# Current_Measurement.net
KiCad netlist of a schematic drawn in Altium Designer
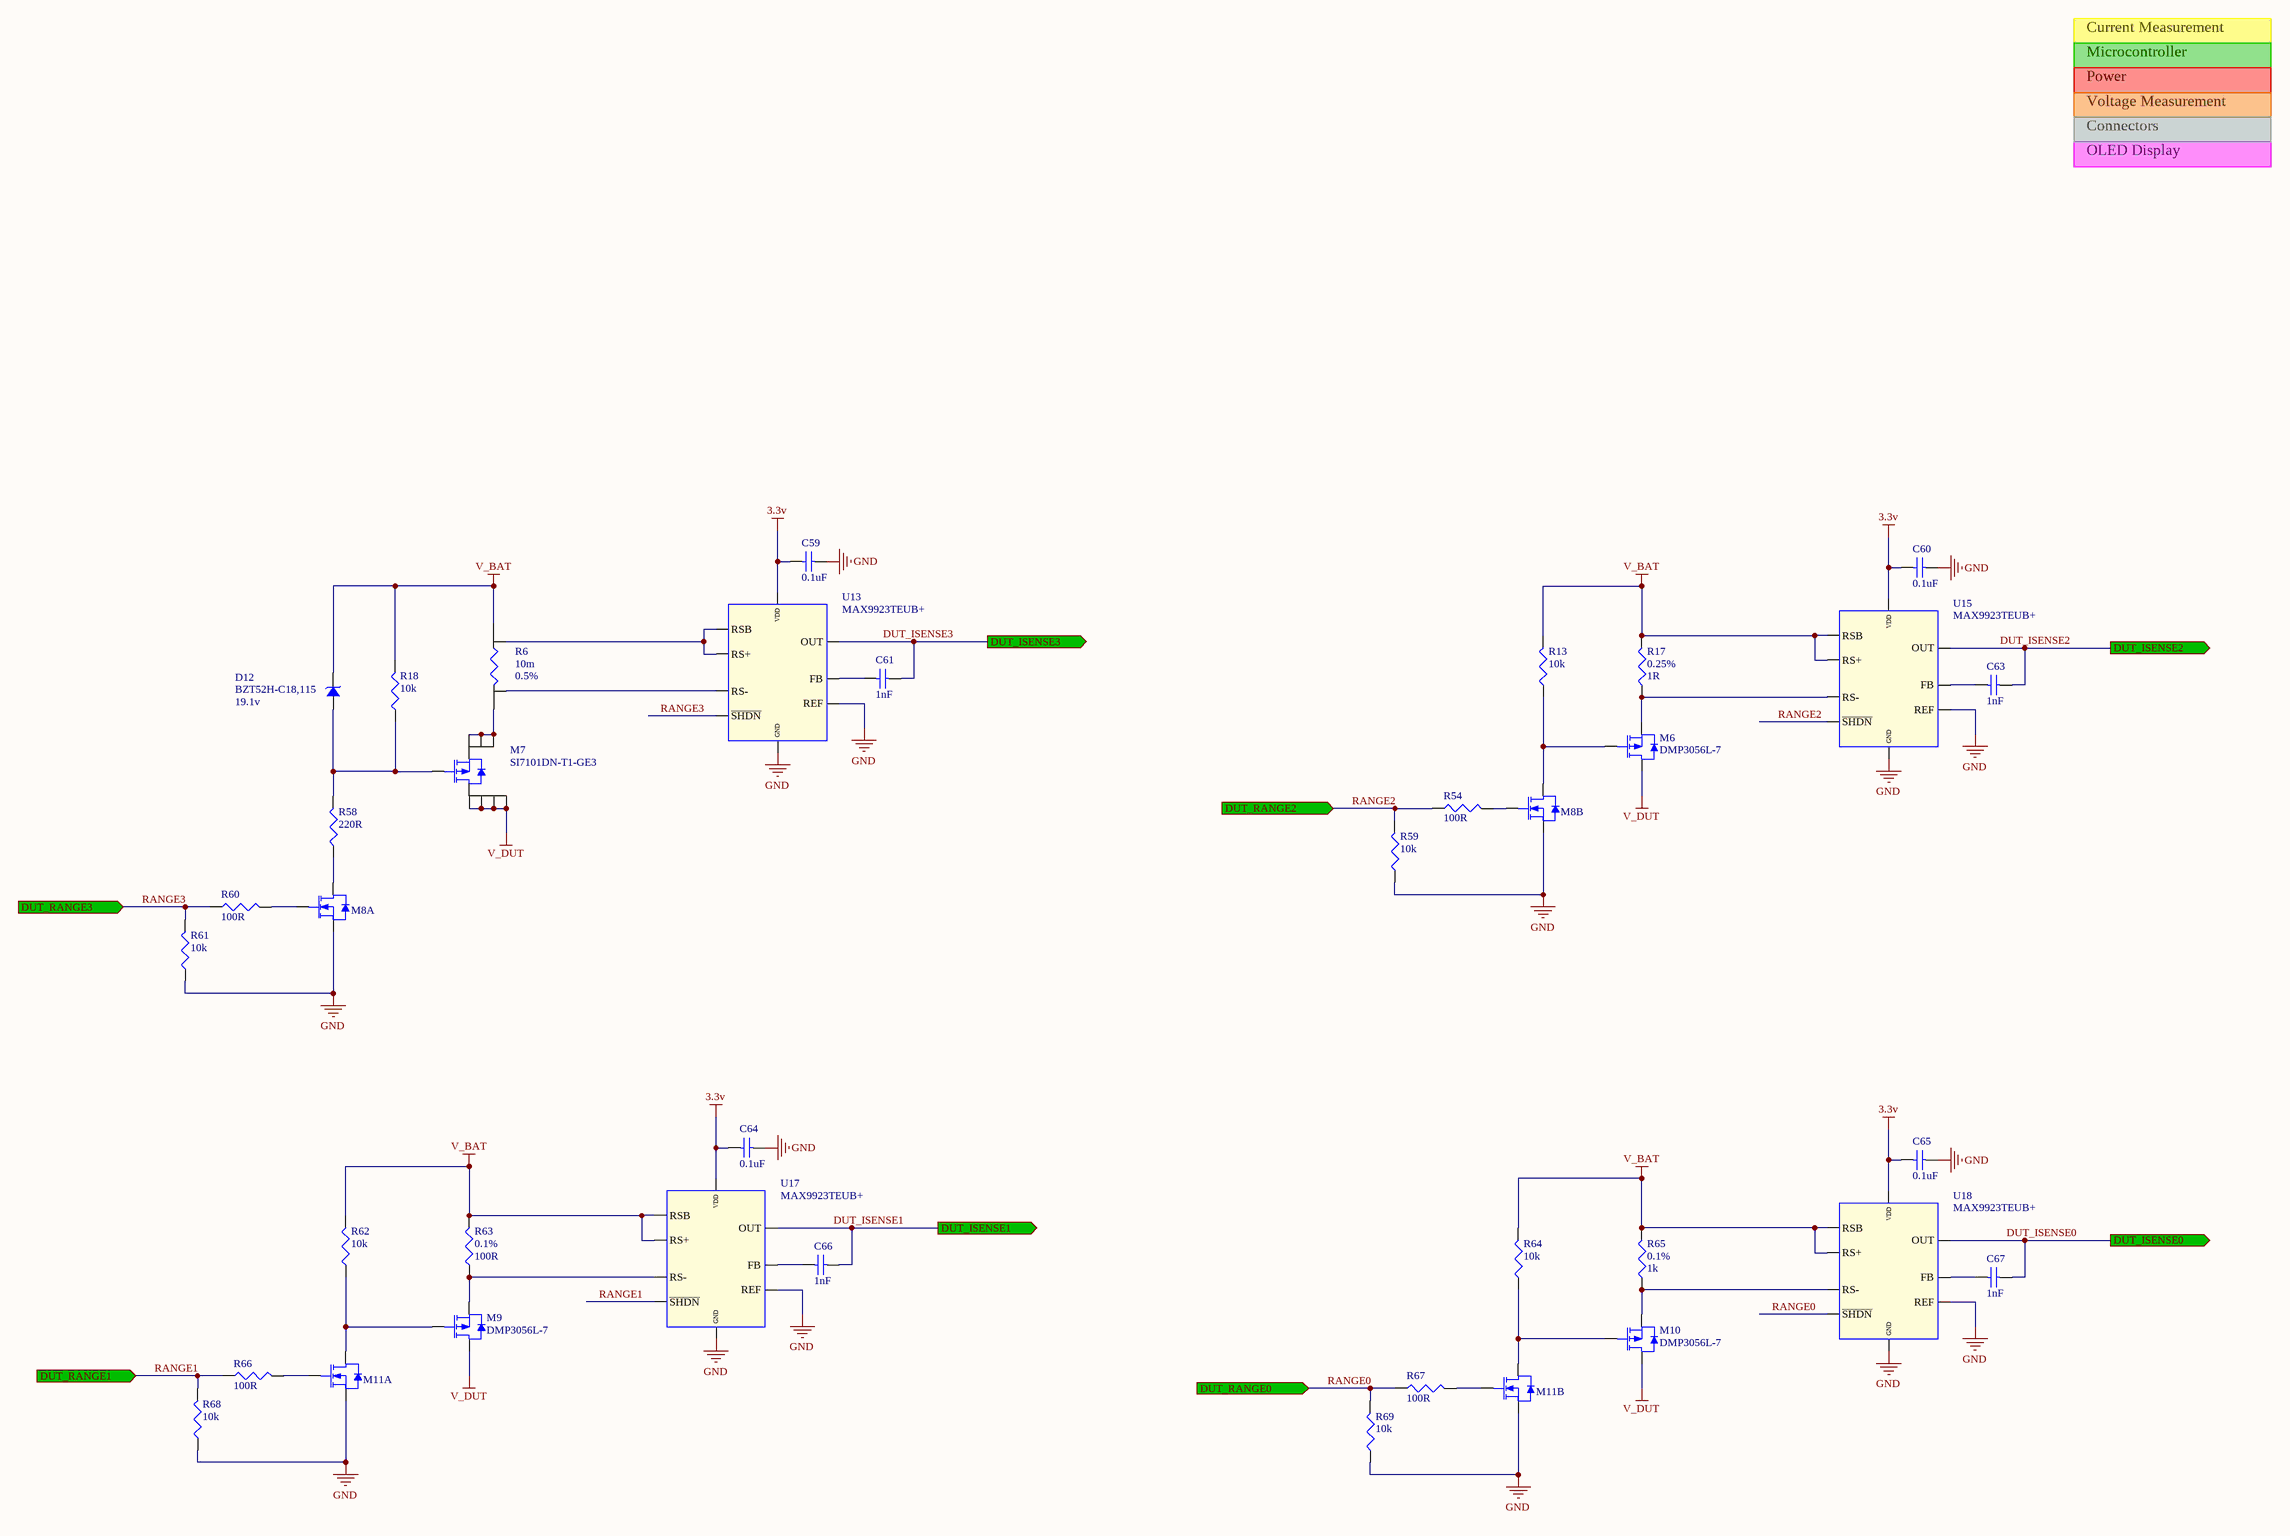
[diagram p0: Current Measurement.SchDoc]

(export (version "E")
  (design (tool "Eeschema 10.0.6"))
  (components
    (comp (ref "C59")
      (value "0.1uF")
      (footprint "CAP0402R")
      (fields (field (name "TOLERANCE") "20%") (field (name "MFG") "Vishay") (field (name "VOLTAGE") "10v"))
      (libsource (lib "Altium Library_EE4951") (part "0.1uF (0402)"))
    )
    (comp (ref "C60")
      (value "0.1uF")
      (footprint "CAP0402R")
      (fields (field (name "TOLERANCE") "20%") (field (name "MFG") "Vishay") (field (name "VOLTAGE") "10v"))
      (libsource (lib "Altium Library_EE4951") (part "0.1uF (0402)"))
    )
    (comp (ref "C61")
      (value "1nF")
      (footprint "CAP0402R")
      (fields (field (name "TOLERANCE") "10%") (field (name "MFG") "Vishay") (field (name "VOLTAGE") "50v"))
      (libsource (lib "Altium Library_EE4951") (part "1nF (0402)"))
    )
    (comp (ref "C63")
      (value "1nF")
      (footprint "CAP0402R")
      (fields (field (name "TOLERANCE") "10%") (field (name "MFG") "Vishay") (field (name "VOLTAGE") "50v"))
      (libsource (lib "Altium Library_EE4951") (part "1nF (0402)"))
    )
    (comp (ref "C64")
      (value "0.1uF")
      (footprint "CAP0402R")
      (fields (field (name "TOLERANCE") "20%") (field (name "MFG") "Vishay") (field (name "VOLTAGE") "10v"))
      (libsource (lib "Altium Library_EE4951") (part "0.1uF (0402)"))
    )
    (comp (ref "C65")
      (value "0.1uF")
      (footprint "CAP0402R")
      (fields (field (name "TOLERANCE") "20%") (field (name "MFG") "Vishay") (field (name "VOLTAGE") "10v"))
      (libsource (lib "Altium Library_EE4951") (part "0.1uF (0402)"))
    )
    (comp (ref "C66")
      (value "1nF")
      (footprint "CAP0402R")
      (fields (field (name "TOLERANCE") "10%") (field (name "MFG") "Vishay") (field (name "VOLTAGE") "50v"))
      (libsource (lib "Altium Library_EE4951") (part "1nF (0402)"))
    )
    (comp (ref "C67")
      (value "1nF")
      (footprint "CAP0402R")
      (fields (field (name "TOLERANCE") "10%") (field (name "MFG") "Vishay") (field (name "VOLTAGE") "50v"))
      (libsource (lib "Altium Library_EE4951") (part "1nF (0402)"))
    )
    (comp (ref "D12")
      (value "BZT52H-C18,115")
      (footprint "SOD-123")
      (description "19.1v Zener Diode")
      (fields (field (name "MFG") "NXP") (field (name "OPER_VOLTAGE") "19.1v"))
      (libsource (lib "Altium Library_EE4951") (part "BZT52H-C18"))
    )
    (comp (ref "M6")
      (value "DMP3056L-7")
      (footprint "SOT23-3M")
      (description "PFET_SINGLE_4.3A_30v")
      (fields (field (name "MFG") "DIODES_INC"))
      (libsource (lib "Altium Library_EE4951") (part "DMP3056L"))
    )
    (comp (ref "M7")
      (value "SI7101DN-T1-GE3")
      (footprint "PowerPAK-1212-8")
      (description "PFET_SINGLE_35A_30v")
      (fields (field (name "MFG") "VISHAY") (field (name "POWER") "52W"))
      (libsource (lib "Altium Library_EE4951") (part "SI7101DN"))
    )
    (comp (ref "M8")
      (value "NX3020NAKV,115")
      (footprint "SOT666-6N")
      (description "NFET_DUAL_200mA_30v")
      (fields (field (name "MFG") "NXP"))
      (libsource (lib "Altium Library") (part "NX3020NAKV"))
    )
    (comp (ref "M9")
      (value "DMP3056L-7")
      (footprint "SOT23-3M")
      (description "PFET_SINGLE_4.3A_30v")
      (fields (field (name "MFG") "DIODES_INC"))
      (libsource (lib "Altium Library_EE4951") (part "DMP3056L"))
    )
    (comp (ref "M10")
      (value "DMP3056L-7")
      (footprint "SOT23-3M")
      (description "PFET_SINGLE_4.3A_30v")
      (fields (field (name "MFG") "DIODES_INC"))
      (libsource (lib "Altium Library_EE4951") (part "DMP3056L"))
    )
    (comp (ref "M11")
      (value "NX3020NAKV,115")
      (footprint "SOT666-6N")
      (description "NFET_DUAL_200mA_30v")
      (fields (field (name "MFG") "NXP"))
      (libsource (lib "Altium Library") (part "NX3020NAKV"))
    )
    (comp (ref "R6")
      (value "10m")
      (footprint "2512 4 Terminal")
      (description "10mR Current Sense - 4-Terminal")
      (fields (field (name "MFG") "VISHAY") (field (name "POWER") "1W") (field (name "TOLERANCE") "0.5%"))
      (libsource (lib "Altium Library_EE4951") (part "10m 0.5% (2512 4-Terminal)"))
    )
    (comp (ref "R13")
      (value "10k")
      (footprint "RES0603R")
      (fields (field (name "TOLERANCE") "1%") (field (name "POWER") "0.1W") (field (name "MFG") "Vishay"))
      (libsource (lib "Altium Library_EE4951") (part "10K (0603)"))
    )
    (comp (ref "R17")
      (value "1R")
      (footprint "RES0805R")
      (fields (field (name "POWER") "100mW") (field (name "MFG") "Bourns") (field (name "TOLERANCE") "0.25%"))
      (libsource (lib "Altium Library_EE4951") (part "1R 0.25% (0805)"))
    )
    (comp (ref "R18")
      (value "10k")
      (footprint "RES0603R")
      (fields (field (name "TOLERANCE") "1%") (field (name "POWER") "0.1W") (field (name "MFG") "Vishay"))
      (libsource (lib "Altium Library_EE4951") (part "10K (0603)"))
    )
    (comp (ref "R54")
      (value "100R")
      (footprint "RES0402R")
      (fields (field (name "TOLERANCE") "1%") (field (name "POWER") "63mW") (field (name "MFG") "Vishay"))
      (libsource (lib "Altium Library") (part "100R (0402)"))
    )
    (comp (ref "R58")
      (value "220R")
      (footprint "RES0603R")
      (fields (field (name "TOLERANCE") "1%") (field (name "POWER") "0.1W") (field (name "MFG") "Vishay"))
      (libsource (lib "Altium Library_EE4951") (part "220R (0603)"))
    )
    (comp (ref "R59")
      (value "10k")
      (footprint "RES0402R")
      (fields (field (name "TOLERANCE") "1%") (field (name "POWER") "63mW") (field (name "MFG") "Vishay"))
      (libsource (lib "Altium Library") (part "10k (0402)"))
    )
    (comp (ref "R60")
      (value "100R")
      (footprint "RES0402R")
      (fields (field (name "TOLERANCE") "1%") (field (name "POWER") "63mW") (field (name "MFG") "Vishay"))
      (libsource (lib "Altium Library") (part "100R (0402)"))
    )
    (comp (ref "R61")
      (value "10k")
      (footprint "RES0402R")
      (fields (field (name "TOLERANCE") "1%") (field (name "POWER") "63mW") (field (name "MFG") "Vishay"))
      (libsource (lib "Altium Library") (part "10k (0402)"))
    )
    (comp (ref "R62")
      (value "10k")
      (footprint "RES0603R")
      (fields (field (name "TOLERANCE") "1%") (field (name "POWER") "0.1W") (field (name "MFG") "Vishay"))
      (libsource (lib "Altium Library_EE4951") (part "10K (0603)"))
    )
    (comp (ref "R63")
      (value "100R")
      (footprint "RES0603W")
      (fields (field (name "POWER") "0.1W") (field (name "MFG") "Vishay") (field (name "TOLERANCE") "0.1%"))
      (libsource (lib "Altium Library_EE4951") (part "100R   0.1% (0603)"))
    )
    (comp (ref "R64")
      (value "10k")
      (footprint "RES0603R")
      (fields (field (name "TOLERANCE") "1%") (field (name "POWER") "0.1W") (field (name "MFG") "Vishay"))
      (libsource (lib "Altium Library_EE4951") (part "10K (0603)"))
    )
    (comp (ref "R65")
      (value "1k")
      (footprint "RES0603W")
      (fields (field (name "POWER") "0.1W") (field (name "MFG") "Vishay") (field (name "TOLERANCE") "0.1%"))
      (libsource (lib "Altium Library_EE4951") (part "1k   0.1% (0603)"))
    )
    (comp (ref "R66")
      (value "100R")
      (footprint "RES0402R")
      (fields (field (name "TOLERANCE") "1%") (field (name "POWER") "63mW") (field (name "MFG") "Vishay"))
      (libsource (lib "Altium Library") (part "100R (0402)"))
    )
    (comp (ref "R67")
      (value "100R")
      (footprint "RES0402R")
      (fields (field (name "TOLERANCE") "1%") (field (name "POWER") "63mW") (field (name "MFG") "Vishay"))
      (libsource (lib "Altium Library") (part "100R (0402)"))
    )
    (comp (ref "R68")
      (value "10k")
      (footprint "RES0402R")
      (fields (field (name "TOLERANCE") "1%") (field (name "POWER") "63mW") (field (name "MFG") "Vishay"))
      (libsource (lib "Altium Library") (part "10k (0402)"))
    )
    (comp (ref "R69")
      (value "10k")
      (footprint "RES0402R")
      (fields (field (name "TOLERANCE") "1%") (field (name "POWER") "63mW") (field (name "MFG") "Vishay"))
      (libsource (lib "Altium Library") (part "10k (0402)"))
    )
    (comp (ref "U13")
      (value "MAX9923TEUB+")
      (footprint "uMAX10")
      (description "Ultra-Precision High Side Current Shunt Amp")
      (fields (field (name "MFG") "MAXIM"))
      (libsource (lib "Altium Library_EE4951") (part "MAX9923TEUB+"))
    )
    (comp (ref "U15")
      (value "MAX9923TEUB+")
      (footprint "uMAX10")
      (description "Ultra-Precision High Side Current Shunt Amp")
      (fields (field (name "MFG") "MAXIM"))
      (libsource (lib "Altium Library_EE4951") (part "MAX9923TEUB+"))
    )
    (comp (ref "U17")
      (value "MAX9923TEUB+")
      (footprint "uMAX10")
      (description "Ultra-Precision High Side Current Shunt Amp")
      (fields (field (name "MFG") "MAXIM"))
      (libsource (lib "Altium Library_EE4951") (part "MAX9923TEUB+"))
    )
    (comp (ref "U18")
      (value "MAX9923TEUB+")
      (footprint "uMAX10")
      (description "Ultra-Precision High Side Current Shunt Amp")
      (fields (field (name "MFG") "MAXIM"))
      (libsource (lib "Altium Library_EE4951") (part "MAX9923TEUB+"))
    )
  )
  (nets
    (net (code "1") (name "/DUT_ISENSE0") (class "Default")
      (node (ref "C67") (pin "2") (pinfunction "2_2") (pintype "passive"))
      (node (ref "U18") (pin "9") (pinfunction "OUT_9") (pintype "passive"))
    )
    (net (code "2") (name "/DUT_ISENSE1") (class "Default")
      (node (ref "C66") (pin "2") (pinfunction "2_2") (pintype "passive"))
      (node (ref "U17") (pin "9") (pinfunction "OUT_9") (pintype "passive"))
    )
    (net (code "3") (name "/DUT_ISENSE2") (class "Default")
      (node (ref "C63") (pin "2") (pinfunction "2_2") (pintype "passive"))
      (node (ref "U15") (pin "9") (pinfunction "OUT_9") (pintype "passive"))
    )
    (net (code "4") (name "/DUT_ISENSE3") (class "Default")
      (node (ref "C61") (pin "2") (pinfunction "2_2") (pintype "passive"))
      (node (ref "U13") (pin "9") (pinfunction "OUT_9") (pintype "passive"))
    )
    (net (code "5") (name "/RANGE0") (class "Default")
      (node (ref "R67") (pin "1") (pinfunction "1_1") (pintype "passive"))
      (node (ref "R69") (pin "2") (pinfunction "2_2") (pintype "passive"))
      (node (ref "U18") (pin "6") (pinfunction "~{SHDN}_6") (pintype "passive"))
    )
    (net (code "6") (name "/RANGE1") (class "Default")
      (node (ref "R66") (pin "1") (pinfunction "1_1") (pintype "passive"))
      (node (ref "R68") (pin "2") (pinfunction "2_2") (pintype "passive"))
      (node (ref "U17") (pin "6") (pinfunction "~{SHDN}_6") (pintype "passive"))
    )
    (net (code "7") (name "/RANGE2") (class "Default")
      (node (ref "R54") (pin "1") (pinfunction "1_1") (pintype "passive"))
      (node (ref "R59") (pin "2") (pinfunction "2_2") (pintype "passive"))
      (node (ref "U15") (pin "6") (pinfunction "~{SHDN}_6") (pintype "passive"))
    )
    (net (code "8") (name "/RANGE3") (class "Default")
      (node (ref "R60") (pin "1") (pinfunction "1_1") (pintype "passive"))
      (node (ref "R61") (pin "2") (pinfunction "2_2") (pintype "passive"))
      (node (ref "U13") (pin "6") (pinfunction "~{SHDN}_6") (pintype "passive"))
    )
    (net (code "9") (name "3.3v") (class "Default")
      (node (ref "C59") (pin "1") (pinfunction "1_1") (pintype "passive"))
      (node (ref "C60") (pin "1") (pinfunction "1_1") (pintype "passive"))
      (node (ref "C64") (pin "1") (pinfunction "1_1") (pintype "passive"))
      (node (ref "C65") (pin "1") (pinfunction "1_1") (pintype "passive"))
      (node (ref "U13") (pin "10") (pinfunction "VDD_10") (pintype "passive"))
      (node (ref "U15") (pin "10") (pinfunction "VDD_10") (pintype "passive"))
      (node (ref "U17") (pin "10") (pinfunction "VDD_10") (pintype "passive"))
      (node (ref "U18") (pin "10") (pinfunction "VDD_10") (pintype "passive"))
    )
    (net (code "10") (name "GND") (class "Default")
      (node (ref "C59") (pin "2") (pinfunction "2_2") (pintype "passive"))
      (node (ref "C60") (pin "2") (pinfunction "2_2") (pintype "passive"))
      (node (ref "C64") (pin "2") (pinfunction "2_2") (pintype "passive"))
      (node (ref "C65") (pin "2") (pinfunction "2_2") (pintype "passive"))
      (node (ref "M11") (pin "1") (pinfunction "S1_1") (pintype "passive"))
      (node (ref "M11") (pin "4") (pinfunction "S2_4") (pintype "passive"))
      (node (ref "M8") (pin "1") (pinfunction "S1_1") (pintype "passive"))
      (node (ref "M8") (pin "4") (pinfunction "S2_4") (pintype "passive"))
      (node (ref "R59") (pin "1") (pinfunction "1_1") (pintype "passive"))
      (node (ref "R61") (pin "1") (pinfunction "1_1") (pintype "passive"))
      (node (ref "R68") (pin "1") (pinfunction "1_1") (pintype "passive"))
      (node (ref "R69") (pin "1") (pinfunction "1_1") (pintype "passive"))
      (node (ref "U13") (pin "5") (pinfunction "GND_5") (pintype "passive"))
      (node (ref "U13") (pin "7") (pinfunction "REF_7") (pintype "passive"))
      (node (ref "U15") (pin "5") (pinfunction "GND_5") (pintype "passive"))
      (node (ref "U15") (pin "7") (pinfunction "REF_7") (pintype "passive"))
      (node (ref "U17") (pin "5") (pinfunction "GND_5") (pintype "passive"))
      (node (ref "U17") (pin "7") (pinfunction "REF_7") (pintype "passive"))
      (node (ref "U18") (pin "5") (pinfunction "GND_5") (pintype "passive"))
      (node (ref "U18") (pin "7") (pinfunction "REF_7") (pintype "passive"))
    )
    (net (code "11") (name "Net-(D12-A)") (class "Default")
      (node (ref "D12") (pin "2") (pinfunction "A_2") (pintype "passive"))
      (node (ref "M7") (pin "4") (pinfunction "4_4") (pintype "passive"))
      (node (ref "R18") (pin "1") (pinfunction "1_1") (pintype "passive"))
      (node (ref "R58") (pin "2") (pinfunction "2_2") (pintype "passive"))
    )
    (net (code "12") (name "Net-(M6-DRAIN)") (class "Default")
      (node (ref "M6") (pin "2") (pinfunction "DRAIN_2") (pintype "passive"))
      (node (ref "R17") (pin "1") (pinfunction "1_1") (pintype "passive"))
      (node (ref "U15") (pin "3") (pinfunction "RS-_3") (pintype "passive"))
    )
    (net (code "13") (name "Net-(M6-GATE)") (class "Default")
      (node (ref "M6") (pin "1") (pinfunction "GATE_1") (pintype "passive"))
      (node (ref "M8") (pin "3") (pinfunction "D2_3") (pintype "passive"))
      (node (ref "R13") (pin "1") (pinfunction "1_1") (pintype "passive"))
    )
    (net (code "14") (name "Net-(M7-Pad1)") (class "Default")
      (node (ref "M7") (pin "1") (pinfunction "1_1") (pintype "passive"))
      (node (ref "M7") (pin "2") (pinfunction "2_2") (pintype "passive"))
      (node (ref "M7") (pin "3") (pinfunction "3_3") (pintype "passive"))
      (node (ref "R6") (pin "1") (pinfunction "1_1") (pintype "passive"))
    )
    (net (code "15") (name "Net-(M8A-D1)") (class "Default")
      (node (ref "M8") (pin "6") (pinfunction "D1_6") (pintype "passive"))
      (node (ref "R58") (pin "1") (pinfunction "1_1") (pintype "passive"))
    )
    (net (code "16") (name "Net-(M8A-G1)") (class "Default")
      (node (ref "M8") (pin "2") (pinfunction "G1_2") (pintype "passive"))
      (node (ref "R60") (pin "2") (pinfunction "2_2") (pintype "passive"))
    )
    (net (code "17") (name "Net-(M8B-G2)") (class "Default")
      (node (ref "M8") (pin "5") (pinfunction "G2_5") (pintype "passive"))
      (node (ref "R54") (pin "2") (pinfunction "2_2") (pintype "passive"))
    )
    (net (code "18") (name "Net-(M9-DRAIN)") (class "Default")
      (node (ref "M9") (pin "2") (pinfunction "DRAIN_2") (pintype "passive"))
      (node (ref "R63") (pin "1") (pinfunction "1_1") (pintype "passive"))
      (node (ref "U17") (pin "3") (pinfunction "RS-_3") (pintype "passive"))
    )
    (net (code "19") (name "Net-(M10-DRAIN)") (class "Default")
      (node (ref "M10") (pin "2") (pinfunction "DRAIN_2") (pintype "passive"))
      (node (ref "R65") (pin "1") (pinfunction "1_1") (pintype "passive"))
      (node (ref "U18") (pin "3") (pinfunction "RS-_3") (pintype "passive"))
    )
    (net (code "20") (name "Net-(M10-GATE)") (class "Default")
      (node (ref "M10") (pin "1") (pinfunction "GATE_1") (pintype "passive"))
      (node (ref "M11") (pin "3") (pinfunction "D2_3") (pintype "passive"))
      (node (ref "R64") (pin "1") (pinfunction "1_1") (pintype "passive"))
    )
    (net (code "21") (name "Net-(M11A-D1)") (class "Default")
      (node (ref "M11") (pin "6") (pinfunction "D1_6") (pintype "passive"))
      (node (ref "M9") (pin "1") (pinfunction "GATE_1") (pintype "passive"))
      (node (ref "R62") (pin "1") (pinfunction "1_1") (pintype "passive"))
    )
    (net (code "22") (name "Net-(M11A-G1)") (class "Default")
      (node (ref "M11") (pin "2") (pinfunction "G1_2") (pintype "passive"))
      (node (ref "R66") (pin "2") (pinfunction "2_2") (pintype "passive"))
    )
    (net (code "23") (name "Net-(M11B-G2)") (class "Default")
      (node (ref "M11") (pin "5") (pinfunction "G2_5") (pintype "passive"))
      (node (ref "R67") (pin "2") (pinfunction "2_2") (pintype "passive"))
    )
    (net (code "24") (name "Net-(U13-FB)") (class "Default")
      (node (ref "C61") (pin "1") (pinfunction "1_1") (pintype "passive"))
      (node (ref "U13") (pin "8") (pinfunction "FB_8") (pintype "passive"))
    )
    (net (code "25") (name "Net-(U13-RS+)") (class "Default")
      (node (ref "R6") (pin "4") (pinfunction "4_4") (pintype "passive"))
      (node (ref "U13") (pin "1") (pinfunction "RSB_1") (pintype "passive"))
      (node (ref "U13") (pin "2") (pinfunction "RS+_2") (pintype "passive"))
    )
    (net (code "26") (name "Net-(U13-RS-)") (class "Default")
      (node (ref "R6") (pin "2") (pinfunction "2_2") (pintype "passive"))
      (node (ref "U13") (pin "3") (pinfunction "RS-_3") (pintype "passive"))
    )
    (net (code "27") (name "Net-(U15-FB)") (class "Default")
      (node (ref "C63") (pin "1") (pinfunction "1_1") (pintype "passive"))
      (node (ref "U15") (pin "8") (pinfunction "FB_8") (pintype "passive"))
    )
    (net (code "28") (name "Net-(U17-FB)") (class "Default")
      (node (ref "C66") (pin "1") (pinfunction "1_1") (pintype "passive"))
      (node (ref "U17") (pin "8") (pinfunction "FB_8") (pintype "passive"))
    )
    (net (code "29") (name "Net-(U18-FB)") (class "Default")
      (node (ref "C67") (pin "1") (pinfunction "1_1") (pintype "passive"))
      (node (ref "U18") (pin "8") (pinfunction "FB_8") (pintype "passive"))
    )
    (net (code "30") (name "V_BAT") (class "Default")
      (node (ref "D12") (pin "1") (pinfunction "K_1") (pintype "passive"))
      (node (ref "R13") (pin "2") (pinfunction "2_2") (pintype "passive"))
      (node (ref "R17") (pin "2") (pinfunction "2_2") (pintype "passive"))
      (node (ref "R18") (pin "2") (pinfunction "2_2") (pintype "passive"))
      (node (ref "R6") (pin "3") (pinfunction "3_3") (pintype "passive"))
      (node (ref "R62") (pin "2") (pinfunction "2_2") (pintype "passive"))
      (node (ref "R63") (pin "2") (pinfunction "2_2") (pintype "passive"))
      (node (ref "R64") (pin "2") (pinfunction "2_2") (pintype "passive"))
      (node (ref "R65") (pin "2") (pinfunction "2_2") (pintype "passive"))
      (node (ref "U15") (pin "1") (pinfunction "RSB_1") (pintype "passive"))
      (node (ref "U15") (pin "2") (pinfunction "RS+_2") (pintype "passive"))
      (node (ref "U17") (pin "1") (pinfunction "RSB_1") (pintype "passive"))
      (node (ref "U17") (pin "2") (pinfunction "RS+_2") (pintype "passive"))
      (node (ref "U18") (pin "1") (pinfunction "RSB_1") (pintype "passive"))
      (node (ref "U18") (pin "2") (pinfunction "RS+_2") (pintype "passive"))
    )
    (net (code "31") (name "V_DUT") (class "Default")
      (node (ref "M10") (pin "3") (pinfunction "SOURCE_3") (pintype "passive"))
      (node (ref "M6") (pin "3") (pinfunction "SOURCE_3") (pintype "passive"))
      (node (ref "M7") (pin "5") (pinfunction "5_5") (pintype "passive"))
      (node (ref "M7") (pin "6") (pinfunction "6_6") (pintype "passive"))
      (node (ref "M7") (pin "7") (pinfunction "7_7") (pintype "passive"))
      (node (ref "M7") (pin "8") (pinfunction "8_8") (pintype "passive"))
      (node (ref "M9") (pin "3") (pinfunction "SOURCE_3") (pintype "passive"))
    )
    (net (code "32") (name "unconnected-(U13-NC-Pad4)") (class "Default")
      (node (ref "U13") (pin "4") (pinfunction "NC_4") (pintype "passive"))
    )
    (net (code "33") (name "unconnected-(U15-NC-Pad4)") (class "Default")
      (node (ref "U15") (pin "4") (pinfunction "NC_4") (pintype "passive"))
    )
    (net (code "34") (name "unconnected-(U17-NC-Pad4)") (class "Default")
      (node (ref "U17") (pin "4") (pinfunction "NC_4") (pintype "passive"))
    )
    (net (code "35") (name "unconnected-(U18-NC-Pad4)") (class "Default")
      (node (ref "U18") (pin "4") (pinfunction "NC_4") (pintype "passive"))
    )
  )
)
